# wctl_wifi.net
KiCad netlist of a schematic drawn in EAGLE
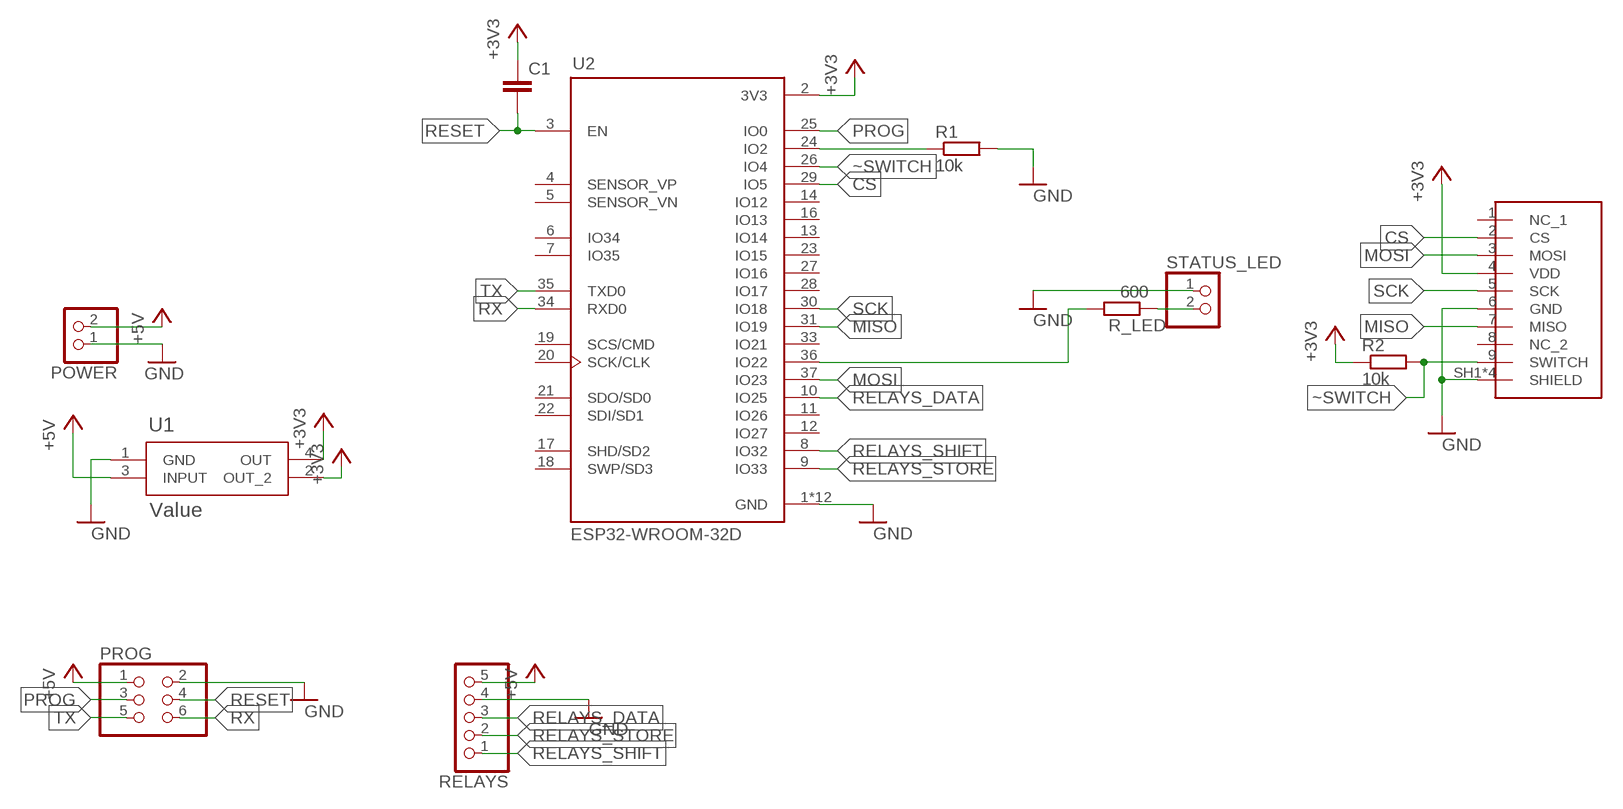
[diagram p0: schematic, sheet 1]

(export (version "E")
  (design (tool "Eeschema 10.0.6"))
  (components
    (comp (ref "C1")
      (value "C-EUC0603")
      (footprint "eagle-import:C0603")
      (libsource (lib "eagle-import") (part "C-EUC0603"))
    )
    (comp (ref "POWER")
      (value "PINHD-1X2")
      (footprint "eagle-import:1X02")
      (libsource (lib "eagle-import") (part "PINHD-1X2"))
    )
    (comp (ref "PROG")
      (value "PINHD-2X3")
      (footprint "eagle-import:2X03")
      (libsource (lib "eagle-import") (part "PINHD-2X3"))
    )
    (comp (ref "R1")
      (value "10k")
      (footprint "eagle-import:R0603")
      (libsource (lib "eagle-import") (part "R-EU_R0603"))
    )
    (comp (ref "R2")
      (value "10k")
      (footprint "eagle-import:R0603")
      (libsource (lib "eagle-import") (part "R-EU_R0603"))
    )
    (comp (ref "RELAYS")
      (value "PINHD-1X5")
      (footprint "eagle-import:1X05")
      (libsource (lib "eagle-import") (part "PINHD-1X5"))
    )
    (comp (ref "R_LED")
      (value "600")
      (footprint "eagle-import:R0603")
      (libsource (lib "eagle-import") (part "R-EU_R0603"))
    )
    (comp (ref "STATUS_LED")
      (value "PINHD-1X2")
      (footprint "eagle-import:1X02")
      (libsource (lib "eagle-import") (part "PINHD-1X2"))
    )
    (comp (ref "U$1")
      (value "SD_SLOT")
      (footprint "eagle-import:SD_SLOT")
      (libsource (lib "eagle-import") (part "SD_SLOT"))
    )
    (comp (ref "U1")
      (value "Value")
      (footprint "eagle-import:DCY0004A_M")
      (fields
        (field (name "MANUFACTURER") "Texas Instruments")
        (field (name "PARTNUMBER") "LM1117IMP-3.3/NOPB")
      )
      (libsource (lib "eagle-import") (part "LM1117MPX-ADJ/NOPBDCY0004A_M"))
    )
    (comp (ref "U2")
      (value "ESP32-WROOM-32D")
      (footprint "eagle-import:MODULE_ESP32-WROOM-32D")
      (fields (field (name "MF") "Espressif Systems"))
      (libsource (lib "eagle-import") (part "ESP32-WROOM-32D"))
    )
  )
  (nets
    (net (code "1") (name "+3V3") (class "Default")
      (node (ref "C1") (pin "1") (pinfunction "1_1") (pintype "passive"))
      (node (ref "R2") (pin "1") (pinfunction "1_1") (pintype "passive"))
      (node (ref "U$1") (pin "4") (pinfunction "VDD_4") (pintype "bidirectional"))
      (node (ref "U1") (pin "2") (pinfunction "OUT_2_2") (pintype "power_in"))
      (node (ref "U1") (pin "4") (pinfunction "OUT_4") (pintype "power_in"))
      (node (ref "U2") (pin "2") (pinfunction "3V3_2") (pintype "power_in"))
    )
    (net (code "2") (name "+5V") (class "Default")
      (node (ref "POWER") (pin "2") (pinfunction "2_2") (pintype "passive"))
      (node (ref "PROG") (pin "1") (pinfunction "1_1") (pintype "passive"))
      (node (ref "RELAYS") (pin "5") (pinfunction "5_5") (pintype "passive"))
      (node (ref "U1") (pin "3") (pinfunction "INPUT_3") (pintype "power_in"))
    )
    (net (code "3") (name "/~{SWITCH}") (class "Default")
      (node (ref "R2") (pin "2") (pinfunction "2_2") (pintype "passive"))
      (node (ref "U$1") (pin "9") (pinfunction "SWITCH_9") (pintype "bidirectional"))
      (node (ref "U2") (pin "26") (pinfunction "IO4_26") (pintype "bidirectional"))
    )
    (net (code "4") (name "CS") (class "Default")
      (node (ref "U$1") (pin "2") (pinfunction "CS_2") (pintype "bidirectional"))
      (node (ref "U2") (pin "29") (pinfunction "IO5_29") (pintype "bidirectional"))
    )
    (net (code "5") (name "GND") (class "Default")
      (node (ref "POWER") (pin "1") (pinfunction "1_1") (pintype "passive"))
      (node (ref "PROG") (pin "2") (pinfunction "2_2") (pintype "passive"))
      (node (ref "R1") (pin "2") (pinfunction "2_2") (pintype "passive"))
      (node (ref "RELAYS") (pin "4") (pinfunction "4_4") (pintype "passive"))
      (node (ref "STATUS_LED") (pin "1") (pinfunction "1_1") (pintype "passive"))
      (node (ref "U$1") (pin "6") (pinfunction "GND_6") (pintype "bidirectional"))
      (node (ref "U$1") (pin "SH1") (pinfunction "SHIELD_SH1") (pintype "bidirectional"))
      (node (ref "U$1") (pin "SH2") (pinfunction "SHIELD_SH2") (pintype "bidirectional"))
      (node (ref "U$1") (pin "SH3") (pinfunction "SHIELD_SH3") (pintype "bidirectional"))
      (node (ref "U$1") (pin "SH4") (pinfunction "SHIELD_SH4") (pintype "bidirectional"))
      (node (ref "U1") (pin "1") (pinfunction "GND_1") (pintype "power_in"))
      (node (ref "U2") (pin "1") (pinfunction "GND_1") (pintype "power_in"))
      (node (ref "U2") (pin "15") (pinfunction "GND_15") (pintype "power_in"))
      (node (ref "U2") (pin "38") (pinfunction "GND_38") (pintype "power_in"))
      (node (ref "U2") (pin "39_1") (pinfunction "GND_39_1") (pintype "power_in"))
      (node (ref "U2") (pin "39_2") (pinfunction "GND_39_2") (pintype "power_in"))
      (node (ref "U2") (pin "39_3") (pinfunction "GND_39_3") (pintype "power_in"))
      (node (ref "U2") (pin "39_4") (pinfunction "GND_39_4") (pintype "power_in"))
      (node (ref "U2") (pin "39_5") (pinfunction "GND_39_5") (pintype "power_in"))
      (node (ref "U2") (pin "39_6") (pinfunction "GND_39_6") (pintype "power_in"))
      (node (ref "U2") (pin "39_7") (pinfunction "GND_39_7") (pintype "power_in"))
      (node (ref "U2") (pin "39_8") (pinfunction "GND_39_8") (pintype "power_in"))
      (node (ref "U2") (pin "39_9") (pinfunction "GND_39_9") (pintype "power_in"))
    )
    (net (code "6") (name "MISO") (class "Default")
      (node (ref "U$1") (pin "7") (pinfunction "MISO_7") (pintype "bidirectional"))
      (node (ref "U2") (pin "31") (pinfunction "IO19_31") (pintype "bidirectional"))
    )
    (net (code "7") (name "MOSI") (class "Default")
      (node (ref "U$1") (pin "3") (pinfunction "MOSI_3") (pintype "bidirectional"))
      (node (ref "U2") (pin "37") (pinfunction "IO23_37") (pintype "bidirectional"))
    )
    (net (code "8") (name "Net-(R_LED-Pad1)") (class "Default")
      (node (ref "R_LED") (pin "1") (pinfunction "1_1") (pintype "passive"))
      (node (ref "STATUS_LED") (pin "2") (pinfunction "2_2") (pintype "passive"))
    )
    (net (code "9") (name "Net-(U2-IO2)") (class "Default")
      (node (ref "R1") (pin "1") (pinfunction "1_1") (pintype "passive"))
      (node (ref "U2") (pin "24") (pinfunction "IO2_24") (pintype "bidirectional"))
    )
    (net (code "10") (name "Net-(U2-IO22)") (class "Default")
      (node (ref "R_LED") (pin "2") (pinfunction "2_2") (pintype "passive"))
      (node (ref "U2") (pin "36") (pinfunction "IO22_36") (pintype "bidirectional"))
    )
    (net (code "11") (name "PROG") (class "Default")
      (node (ref "PROG") (pin "3") (pinfunction "3_3") (pintype "passive"))
      (node (ref "U2") (pin "25") (pinfunction "IO0_25") (pintype "bidirectional"))
    )
    (net (code "12") (name "RELAYS_DATA") (class "Default")
      (node (ref "RELAYS") (pin "3") (pinfunction "3_3") (pintype "passive"))
      (node (ref "U2") (pin "10") (pinfunction "IO25_10") (pintype "bidirectional"))
    )
    (net (code "13") (name "RELAYS_SHIFT") (class "Default")
      (node (ref "RELAYS") (pin "1") (pinfunction "1_1") (pintype "passive"))
      (node (ref "U2") (pin "8") (pinfunction "IO32_8") (pintype "bidirectional"))
    )
    (net (code "14") (name "RELAYS_STORE") (class "Default")
      (node (ref "RELAYS") (pin "2") (pinfunction "2_2") (pintype "passive"))
      (node (ref "U2") (pin "9") (pinfunction "IO33_9") (pintype "bidirectional"))
    )
    (net (code "15") (name "RESET") (class "Default")
      (node (ref "C1") (pin "2") (pinfunction "2_2") (pintype "passive"))
      (node (ref "PROG") (pin "4") (pinfunction "4_4") (pintype "passive"))
      (node (ref "U2") (pin "3") (pinfunction "EN_3") (pintype "input"))
    )
    (net (code "16") (name "RX") (class "Default")
      (node (ref "PROG") (pin "6") (pinfunction "6_6") (pintype "passive"))
      (node (ref "U2") (pin "34") (pinfunction "RXD0_34") (pintype "bidirectional"))
    )
    (net (code "17") (name "SCK") (class "Default")
      (node (ref "U$1") (pin "5") (pinfunction "SCK_5") (pintype "bidirectional"))
      (node (ref "U2") (pin "30") (pinfunction "IO18_30") (pintype "bidirectional"))
    )
    (net (code "18") (name "TX") (class "Default")
      (node (ref "PROG") (pin "5") (pinfunction "5_5") (pintype "passive"))
      (node (ref "U2") (pin "35") (pinfunction "TXD0_35") (pintype "bidirectional"))
    )
    (net (code "19") (name "unconnected-(U$1-NC_1-Pad1)") (class "Default")
      (node (ref "U$1") (pin "1") (pinfunction "NC_1_1") (pintype "bidirectional"))
    )
    (net (code "20") (name "unconnected-(U$1-NC_2-Pad8)") (class "Default")
      (node (ref "U$1") (pin "8") (pinfunction "NC_2_8") (pintype "bidirectional"))
    )
    (net (code "21") (name "unconnected-(U2-IO12-Pad14)") (class "Default")
      (node (ref "U2") (pin "14") (pinfunction "IO12_14") (pintype "bidirectional"))
    )
    (net (code "22") (name "unconnected-(U2-IO13-Pad16)") (class "Default")
      (node (ref "U2") (pin "16") (pinfunction "IO13_16") (pintype "bidirectional"))
    )
    (net (code "23") (name "unconnected-(U2-IO14-Pad13)") (class "Default")
      (node (ref "U2") (pin "13") (pinfunction "IO14_13") (pintype "bidirectional"))
    )
    (net (code "24") (name "unconnected-(U2-IO15-Pad23)") (class "Default")
      (node (ref "U2") (pin "23") (pinfunction "IO15_23") (pintype "bidirectional"))
    )
    (net (code "25") (name "unconnected-(U2-IO16-Pad27)") (class "Default")
      (node (ref "U2") (pin "27") (pinfunction "IO16_27") (pintype "bidirectional"))
    )
    (net (code "26") (name "unconnected-(U2-IO17-Pad28)") (class "Default")
      (node (ref "U2") (pin "28") (pinfunction "IO17_28") (pintype "bidirectional"))
    )
    (net (code "27") (name "unconnected-(U2-IO21-Pad33)") (class "Default")
      (node (ref "U2") (pin "33") (pinfunction "IO21_33") (pintype "bidirectional"))
    )
    (net (code "28") (name "unconnected-(U2-IO26-Pad11)") (class "Default")
      (node (ref "U2") (pin "11") (pinfunction "IO26_11") (pintype "bidirectional"))
    )
    (net (code "29") (name "unconnected-(U2-IO27-Pad12)") (class "Default")
      (node (ref "U2") (pin "12") (pinfunction "IO27_12") (pintype "bidirectional"))
    )
    (net (code "30") (name "unconnected-(U2-IO34-Pad6)") (class "Default")
      (node (ref "U2") (pin "6") (pinfunction "IO34_6") (pintype "input"))
    )
    (net (code "31") (name "unconnected-(U2-IO35-Pad7)") (class "Default")
      (node (ref "U2") (pin "7") (pinfunction "IO35_7") (pintype "input"))
    )
    (net (code "32") (name "unconnected-(U2-SCK{slash}CLK-Pad20)") (class "Default")
      (node (ref "U2") (pin "20") (pinfunction "SCK/CLK_20") (pintype "bidirectional"))
    )
    (net (code "33") (name "unconnected-(U2-SCS{slash}CMD-Pad19)") (class "Default")
      (node (ref "U2") (pin "19") (pinfunction "SCS/CMD_19") (pintype "bidirectional"))
    )
    (net (code "34") (name "unconnected-(U2-SDI{slash}SD1-Pad22)") (class "Default")
      (node (ref "U2") (pin "22") (pinfunction "SDI/SD1_22") (pintype "bidirectional"))
    )
    (net (code "35") (name "unconnected-(U2-SDO{slash}SD0-Pad21)") (class "Default")
      (node (ref "U2") (pin "21") (pinfunction "SDO/SD0_21") (pintype "bidirectional"))
    )
    (net (code "36") (name "unconnected-(U2-SENSOR_VN-Pad5)") (class "Default")
      (node (ref "U2") (pin "5") (pinfunction "SENSOR_VN_5") (pintype "input"))
    )
    (net (code "37") (name "unconnected-(U2-SENSOR_VP-Pad4)") (class "Default")
      (node (ref "U2") (pin "4") (pinfunction "SENSOR_VP_4") (pintype "input"))
    )
    (net (code "38") (name "unconnected-(U2-SHD{slash}SD2-Pad17)") (class "Default")
      (node (ref "U2") (pin "17") (pinfunction "SHD/SD2_17") (pintype "bidirectional"))
    )
    (net (code "39") (name "unconnected-(U2-SWP{slash}SD3-Pad18)") (class "Default")
      (node (ref "U2") (pin "18") (pinfunction "SWP/SD3_18") (pintype "bidirectional"))
    )
  )
)
